# ENC_card.net
KiCad netlist of a schematic drawn in EAGLE
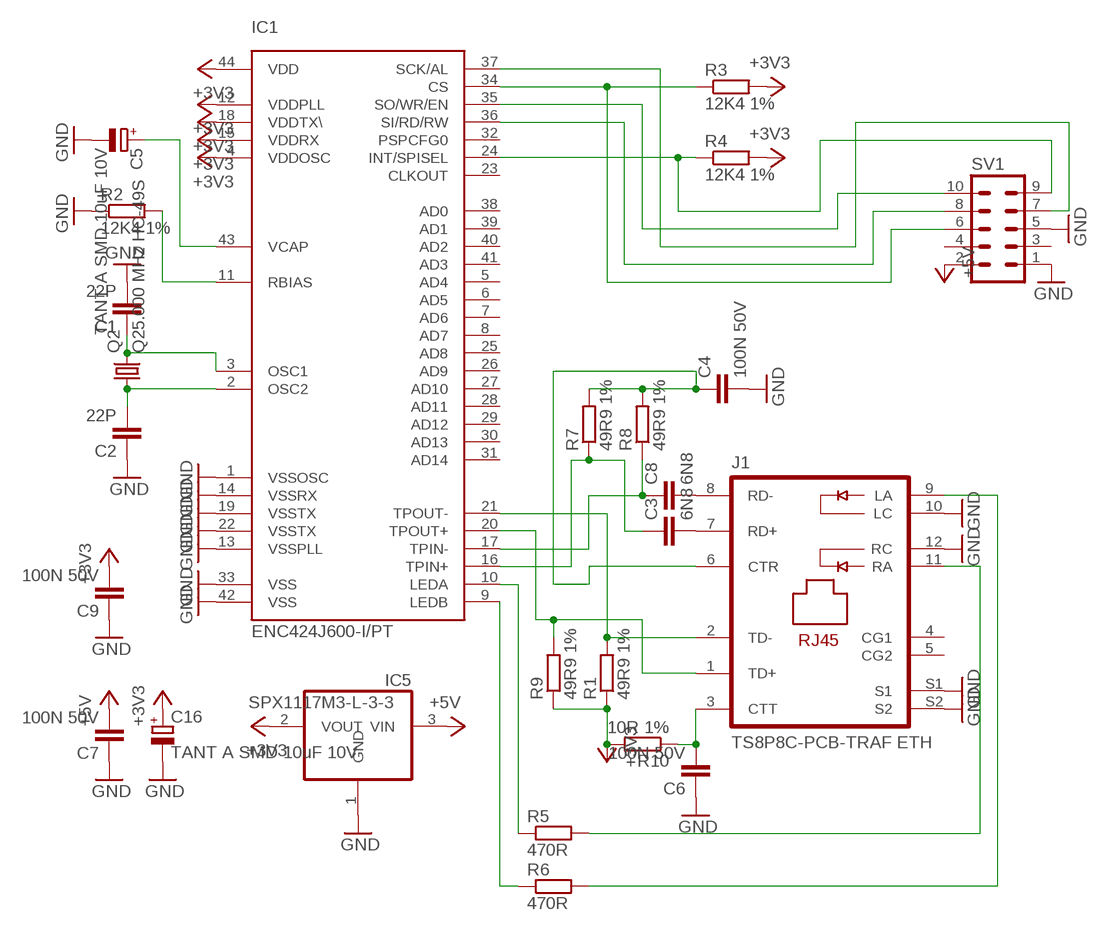
[diagram p0: schematic, sheet 1]

(export (version "E")
  (design (tool "Eeschema 10.0.6"))
  (components
    (comp (ref "C1")
      (value "22P")
      (footprint "eagle-import:C0805")
      (libsource (lib "eagle-import") (part "C-EUC0805"))
    )
    (comp (ref "C2")
      (value "22P")
      (footprint "eagle-import:C0805")
      (libsource (lib "eagle-import") (part "C-EUC0805"))
    )
    (comp (ref "C3")
      (value "6N8")
      (footprint "eagle-import:C0805")
      (libsource (lib "eagle-import") (part "C-EUC0805"))
    )
    (comp (ref "C4")
      (value "100N 50V")
      (footprint "eagle-import:C0805")
      (libsource (lib "eagle-import") (part "C-EUC0805"))
    )
    (comp (ref "C5")
      (value "TANT A SMD 10uF 10V")
      (footprint "eagle-import:SMC_A")
      (libsource (lib "eagle-import") (part "CPOL-EUSMCA"))
    )
    (comp (ref "C6")
      (value "100N 50V")
      (footprint "eagle-import:C0805")
      (libsource (lib "eagle-import") (part "C-EUC0805"))
    )
    (comp (ref "C7")
      (value "100N 50V")
      (footprint "eagle-import:C0805")
      (libsource (lib "eagle-import") (part "C-EUC0805"))
    )
    (comp (ref "C8")
      (value "6N8")
      (footprint "eagle-import:C0805")
      (libsource (lib "eagle-import") (part "C-EUC0805"))
    )
    (comp (ref "C9")
      (value "100N 50V")
      (footprint "eagle-import:C0805")
      (libsource (lib "eagle-import") (part "C-EUC0805"))
    )
    (comp (ref "C16")
      (value "TANT A SMD 10uF 10V")
      (footprint "eagle-import:SMC_A")
      (libsource (lib "eagle-import") (part "CPOL-EUSMCA"))
    )
    (comp (ref "IC1")
      (value "ENC424J600-I/PT")
      (footprint "eagle-import:TQFP44")
      (libsource (lib "eagle-import") (part "ENC424J600-I/PT"))
    )
    (comp (ref "IC5")
      (value "SPX1117M3-L-3-3")
      (footprint "eagle-import:SOT223")
      (fields (field (name "MPN") "REG1117"))
      (libsource (lib "eagle-import") (part "REG1117"))
    )
    (comp (ref "J1")
      (value "TS8P8C-PCB-TRAF ETH")
      (footprint "eagle-import:PJ-J0")
      (libsource (lib "eagle-import") (part "J0026"))
    )
    (comp (ref "Q2")
      (value "Q25.000 MHz HC-49S")
      (footprint "eagle-import:HC49_S")
      (libsource (lib "eagle-import") (part "CRYSTALHC49S"))
    )
    (comp (ref "R1")
      (value "49R9 1%")
      (footprint "eagle-import:R0805")
      (libsource (lib "eagle-import") (part "R-EU_R0805"))
    )
    (comp (ref "R2")
      (value "12K4 1%")
      (footprint "eagle-import:R0805")
      (libsource (lib "eagle-import") (part "R-EU_R0805"))
    )
    (comp (ref "R3")
      (value "12K4 1%")
      (footprint "eagle-import:R0805")
      (libsource (lib "eagle-import") (part "R-EU_R0805"))
    )
    (comp (ref "R4")
      (value "12K4 1%")
      (footprint "eagle-import:R0805")
      (libsource (lib "eagle-import") (part "R-EU_R0805"))
    )
    (comp (ref "R5")
      (value "470R")
      (footprint "eagle-import:R0805")
      (libsource (lib "eagle-import") (part "R-EU_R0805"))
    )
    (comp (ref "R6")
      (value "470R")
      (footprint "eagle-import:R0805")
      (libsource (lib "eagle-import") (part "R-EU_R0805"))
    )
    (comp (ref "R7")
      (value "49R9 1%")
      (footprint "eagle-import:R0805")
      (libsource (lib "eagle-import") (part "R-EU_R0805"))
    )
    (comp (ref "R8")
      (value "49R9 1%")
      (footprint "eagle-import:R0805")
      (libsource (lib "eagle-import") (part "R-EU_R0805"))
    )
    (comp (ref "R9")
      (value "49R9 1%")
      (footprint "eagle-import:R0805")
      (libsource (lib "eagle-import") (part "R-EU_R0805"))
    )
    (comp (ref "R10")
      (value "10R 1%")
      (footprint "eagle-import:R0805")
      (libsource (lib "eagle-import") (part "R-EU_R0805"))
    )
    (comp (ref "SV1")
      (value "ML10L")
      (footprint "eagle-import:ML10L")
      (libsource (lib "eagle-import") (part "ML10L"))
    )
  )
  (nets
    (net (code "1") (name "+3V3") (class "Default")
      (node (ref "C16") (pin "+") (pinfunction "+_+") (pintype "passive"))
      (node (ref "C9") (pin "2") (pinfunction "2_2") (pintype "passive"))
      (node (ref "IC1") (pin "12") (pinfunction "VDDPLL_12") (pintype "power_in"))
      (node (ref "IC1") (pin "15") (pinfunction "VDDRX_15") (pintype "power_in"))
      (node (ref "IC1") (pin "18") (pinfunction "VDDTX\\_18") (pintype "power_in"))
      (node (ref "IC1") (pin "4") (pinfunction "VDDOSC_4") (pintype "power_in"))
      (node (ref "IC1") (pin "44") (pinfunction "VDD_44") (pintype "power_in"))
      (node (ref "IC5") (pin "2") (pinfunction "VOUT_2") (pintype "output"))
      (node (ref "R1") (pin "1") (pinfunction "1_1") (pintype "passive"))
      (node (ref "R10") (pin "2") (pinfunction "2_2") (pintype "passive"))
      (node (ref "R3") (pin "2") (pinfunction "2_2") (pintype "passive"))
      (node (ref "R4") (pin "2") (pinfunction "2_2") (pintype "passive"))
      (node (ref "R9") (pin "1") (pinfunction "1_1") (pintype "passive"))
    )
    (net (code "2") (name "+5V") (class "Default")
      (node (ref "C7") (pin "2") (pinfunction "2_2") (pintype "passive"))
      (node (ref "IC5") (pin "3") (pinfunction "VIN_3") (pintype "input"))
      (node (ref "SV1") (pin "2") (pinfunction "2_2") (pintype "passive"))
    )
    (net (code "3") (name "GND") (class "Default")
      (node (ref "C1") (pin "2") (pinfunction "2_2") (pintype "passive"))
      (node (ref "C16") (pin "-") (pinfunction "-_-") (pintype "passive"))
      (node (ref "C2") (pin "1") (pinfunction "1_1") (pintype "passive"))
      (node (ref "C4") (pin "2") (pinfunction "2_2") (pintype "passive"))
      (node (ref "C5") (pin "-") (pinfunction "-_-") (pintype "passive"))
      (node (ref "C6") (pin "1") (pinfunction "1_1") (pintype "passive"))
      (node (ref "C7") (pin "1") (pinfunction "1_1") (pintype "passive"))
      (node (ref "C9") (pin "1") (pinfunction "1_1") (pintype "passive"))
      (node (ref "IC1") (pin "1") (pinfunction "VSSOSC_1") (pintype "power_in"))
      (node (ref "IC1") (pin "13") (pinfunction "VSSPLL_13") (pintype "power_in"))
      (node (ref "IC1") (pin "14") (pinfunction "VSSRX_14") (pintype "power_in"))
      (node (ref "IC1") (pin "19") (pinfunction "VSSTX_19") (pintype "power_in"))
      (node (ref "IC1") (pin "22") (pinfunction "VSSTX_22") (pintype "power_in"))
      (node (ref "IC1") (pin "33") (pinfunction "VSS_33") (pintype "power_in"))
      (node (ref "IC1") (pin "42") (pinfunction "VSS_42") (pintype "power_in"))
      (node (ref "IC5") (pin "1") (pinfunction "GND_1") (pintype "power_in"))
      (node (ref "J1") (pin "10") (pinfunction "LC_10") (pintype "passive"))
      (node (ref "J1") (pin "12") (pinfunction "RC_12") (pintype "passive"))
      (node (ref "J1") (pin "S1") (pinfunction "S1_S1") (pintype "passive"))
      (node (ref "J1") (pin "S2") (pinfunction "S2_S2") (pintype "passive"))
      (node (ref "R2") (pin "1") (pinfunction "1_1") (pintype "passive"))
      (node (ref "SV1") (pin "1") (pinfunction "1_1") (pintype "passive"))
      (node (ref "SV1") (pin "5") (pinfunction "5_5") (pintype "passive"))
    )
    (net (code "4") (name "Net-(IC1-CS)") (class "Default")
      (node (ref "IC1") (pin "34") (pinfunction "CS_34") (pintype "input"))
      (node (ref "R3") (pin "1") (pinfunction "1_1") (pintype "passive"))
      (node (ref "SV1") (pin "6") (pinfunction "6_6") (pintype "passive"))
    )
    (net (code "5") (name "Net-(IC1-INT{slash}SPISEL)") (class "Default")
      (node (ref "IC1") (pin "24") (pinfunction "INT/SPISEL_24") (pintype "bidirectional"))
      (node (ref "R4") (pin "1") (pinfunction "1_1") (pintype "passive"))
      (node (ref "SV1") (pin "9") (pinfunction "9_9") (pintype "passive"))
    )
    (net (code "6") (name "Net-(IC1-LEDA)") (class "Default")
      (node (ref "IC1") (pin "10") (pinfunction "LEDA_10") (pintype "output"))
      (node (ref "R5") (pin "1") (pinfunction "1_1") (pintype "passive"))
    )
    (net (code "7") (name "Net-(IC1-LEDB)") (class "Default")
      (node (ref "IC1") (pin "9") (pinfunction "LEDB_9") (pintype "output"))
      (node (ref "R6") (pin "1") (pinfunction "1_1") (pintype "passive"))
    )
    (net (code "8") (name "Net-(IC1-OSC1)") (class "Default")
      (node (ref "C1") (pin "1") (pinfunction "1_1") (pintype "passive"))
      (node (ref "IC1") (pin "3") (pinfunction "OSC1_3") (pintype "bidirectional"))
      (node (ref "Q2") (pin "2") (pinfunction "2_2") (pintype "passive"))
    )
    (net (code "9") (name "Net-(IC1-OSC2)") (class "Default")
      (node (ref "C2") (pin "2") (pinfunction "2_2") (pintype "passive"))
      (node (ref "IC1") (pin "2") (pinfunction "OSC2_2") (pintype "bidirectional"))
      (node (ref "Q2") (pin "1") (pinfunction "1_1") (pintype "passive"))
    )
    (net (code "10") (name "Net-(IC1-RBIAS)") (class "Default")
      (node (ref "IC1") (pin "11") (pinfunction "RBIAS_11") (pintype "bidirectional"))
      (node (ref "R2") (pin "2") (pinfunction "2_2") (pintype "passive"))
    )
    (net (code "11") (name "Net-(IC1-SCK{slash}AL)") (class "Default")
      (node (ref "IC1") (pin "37") (pinfunction "SCK/AL_37") (pintype "input"))
      (node (ref "SV1") (pin "7") (pinfunction "7_7") (pintype "passive"))
    )
    (net (code "12") (name "Net-(IC1-SI{slash}RD{slash}RW)") (class "Default")
      (node (ref "IC1") (pin "36") (pinfunction "SI/RD/RW_36") (pintype "bidirectional"))
      (node (ref "SV1") (pin "8") (pinfunction "8_8") (pintype "passive"))
    )
    (net (code "13") (name "Net-(IC1-SO{slash}WR{slash}EN)") (class "Default")
      (node (ref "IC1") (pin "35") (pinfunction "SO/WR/EN_35") (pintype "bidirectional"))
      (node (ref "SV1") (pin "10") (pinfunction "10_10") (pintype "passive"))
    )
    (net (code "14") (name "Net-(IC1-TPIN+)") (class "Default")
      (node (ref "C3") (pin "1") (pinfunction "1_1") (pintype "passive"))
      (node (ref "IC1") (pin "16") (pinfunction "TPIN+_16") (pintype "input"))
      (node (ref "R7") (pin "1") (pinfunction "1_1") (pintype "passive"))
    )
    (net (code "15") (name "Net-(IC1-TPIN-)") (class "Default")
      (node (ref "C8") (pin "1") (pinfunction "1_1") (pintype "passive"))
      (node (ref "IC1") (pin "17") (pinfunction "TPIN-_17") (pintype "input"))
      (node (ref "R8") (pin "1") (pinfunction "1_1") (pintype "passive"))
    )
    (net (code "16") (name "Net-(IC1-TPOUT+)") (class "Default")
      (node (ref "IC1") (pin "20") (pinfunction "TPOUT+_20") (pintype "output"))
      (node (ref "J1") (pin "1") (pinfunction "TD+_1") (pintype "bidirectional"))
      (node (ref "R9") (pin "2") (pinfunction "2_2") (pintype "passive"))
    )
    (net (code "17") (name "Net-(IC1-TPOUT-)") (class "Default")
      (node (ref "IC1") (pin "21") (pinfunction "TPOUT-_21") (pintype "output"))
      (node (ref "J1") (pin "2") (pinfunction "TD-_2") (pintype "bidirectional"))
      (node (ref "R1") (pin "2") (pinfunction "2_2") (pintype "passive"))
    )
    (net (code "18") (name "Net-(IC1-VCAP)") (class "Default")
      (node (ref "C5") (pin "+") (pinfunction "+_+") (pintype "passive"))
      (node (ref "IC1") (pin "43") (pinfunction "VCAP_43") (pintype "bidirectional"))
    )
    (net (code "19") (name "Net-(J1-CTR)") (class "Default")
      (node (ref "C4") (pin "1") (pinfunction "1_1") (pintype "passive"))
      (node (ref "J1") (pin "6") (pinfunction "CTR_6") (pintype "bidirectional"))
      (node (ref "R7") (pin "2") (pinfunction "2_2") (pintype "passive"))
      (node (ref "R8") (pin "2") (pinfunction "2_2") (pintype "passive"))
    )
    (net (code "20") (name "Net-(J1-CTT)") (class "Default")
      (node (ref "C6") (pin "2") (pinfunction "2_2") (pintype "passive"))
      (node (ref "J1") (pin "3") (pinfunction "CTT_3") (pintype "bidirectional"))
      (node (ref "R10") (pin "1") (pinfunction "1_1") (pintype "passive"))
    )
    (net (code "21") (name "Net-(J1-LA)") (class "Default")
      (node (ref "J1") (pin "9") (pinfunction "LA_9") (pintype "passive"))
      (node (ref "R6") (pin "2") (pinfunction "2_2") (pintype "passive"))
    )
    (net (code "22") (name "Net-(J1-RA)") (class "Default")
      (node (ref "J1") (pin "11") (pinfunction "RA_11") (pintype "passive"))
      (node (ref "R5") (pin "2") (pinfunction "2_2") (pintype "passive"))
    )
    (net (code "23") (name "Net-(J1-RD+)") (class "Default")
      (node (ref "C3") (pin "2") (pinfunction "2_2") (pintype "passive"))
      (node (ref "J1") (pin "7") (pinfunction "RD+_7") (pintype "bidirectional"))
    )
    (net (code "24") (name "Net-(J1-RD-)") (class "Default")
      (node (ref "C8") (pin "2") (pinfunction "2_2") (pintype "passive"))
      (node (ref "J1") (pin "8") (pinfunction "RD-_8") (pintype "bidirectional"))
    )
    (net (code "25") (name "unconnected-(IC1-AD0-Pad38)") (class "Default")
      (node (ref "IC1") (pin "38") (pinfunction "AD0_38") (pintype "bidirectional"))
    )
    (net (code "26") (name "unconnected-(IC1-AD1-Pad39)") (class "Default")
      (node (ref "IC1") (pin "39") (pinfunction "AD1_39") (pintype "bidirectional"))
    )
    (net (code "27") (name "unconnected-(IC1-AD2-Pad40)") (class "Default")
      (node (ref "IC1") (pin "40") (pinfunction "AD2_40") (pintype "bidirectional"))
    )
    (net (code "28") (name "unconnected-(IC1-AD3-Pad41)") (class "Default")
      (node (ref "IC1") (pin "41") (pinfunction "AD3_41") (pintype "bidirectional"))
    )
    (net (code "29") (name "unconnected-(IC1-AD4-Pad5)") (class "Default")
      (node (ref "IC1") (pin "5") (pinfunction "AD4_5") (pintype "bidirectional"))
    )
    (net (code "30") (name "unconnected-(IC1-AD5-Pad6)") (class "Default")
      (node (ref "IC1") (pin "6") (pinfunction "AD5_6") (pintype "bidirectional"))
    )
    (net (code "31") (name "unconnected-(IC1-AD6-Pad7)") (class "Default")
      (node (ref "IC1") (pin "7") (pinfunction "AD6_7") (pintype "bidirectional"))
    )
    (net (code "32") (name "unconnected-(IC1-AD7-Pad8)") (class "Default")
      (node (ref "IC1") (pin "8") (pinfunction "AD7_8") (pintype "bidirectional"))
    )
    (net (code "33") (name "unconnected-(IC1-AD8-Pad25)") (class "Default")
      (node (ref "IC1") (pin "25") (pinfunction "AD8_25") (pintype "bidirectional"))
    )
    (net (code "34") (name "unconnected-(IC1-AD9-Pad26)") (class "Default")
      (node (ref "IC1") (pin "26") (pinfunction "AD9_26") (pintype "bidirectional"))
    )
    (net (code "35") (name "unconnected-(IC1-AD10-Pad27)") (class "Default")
      (node (ref "IC1") (pin "27") (pinfunction "AD10_27") (pintype "bidirectional"))
    )
    (net (code "36") (name "unconnected-(IC1-AD11-Pad28)") (class "Default")
      (node (ref "IC1") (pin "28") (pinfunction "AD11_28") (pintype "bidirectional"))
    )
    (net (code "37") (name "unconnected-(IC1-AD12-Pad29)") (class "Default")
      (node (ref "IC1") (pin "29") (pinfunction "AD12_29") (pintype "bidirectional"))
    )
    (net (code "38") (name "unconnected-(IC1-AD13-Pad30)") (class "Default")
      (node (ref "IC1") (pin "30") (pinfunction "AD13_30") (pintype "bidirectional"))
    )
    (net (code "39") (name "unconnected-(IC1-AD14-Pad31)") (class "Default")
      (node (ref "IC1") (pin "31") (pinfunction "AD14_31") (pintype "bidirectional"))
    )
    (net (code "40") (name "unconnected-(IC1-CLKOUT-Pad23)") (class "Default")
      (node (ref "IC1") (pin "23") (pinfunction "CLKOUT_23") (pintype "output"))
    )
    (net (code "41") (name "unconnected-(IC1-PSPCFG0-Pad32)") (class "Default")
      (node (ref "IC1") (pin "32") (pinfunction "PSPCFG0_32") (pintype "input"))
    )
    (net (code "42") (name "unconnected-(J1-CG1-Pad4)") (class "Default")
      (node (ref "J1") (pin "4") (pinfunction "CG1_4") (pintype "passive"))
    )
    (net (code "43") (name "unconnected-(J1-CG2-Pad5)") (class "Default")
      (node (ref "J1") (pin "5") (pinfunction "CG2_5") (pintype "passive"))
    )
    (net (code "44") (name "unconnected-(SV1-Pad3)") (class "Default")
      (node (ref "SV1") (pin "3") (pinfunction "3_3") (pintype "passive"))
    )
    (net (code "45") (name "unconnected-(SV1-Pad4)") (class "Default")
      (node (ref "SV1") (pin "4") (pinfunction "4_4") (pintype "passive"))
    )
  )
)
